# USDA_Project.net
KiCad netlist of a schematic drawn in EAGLE
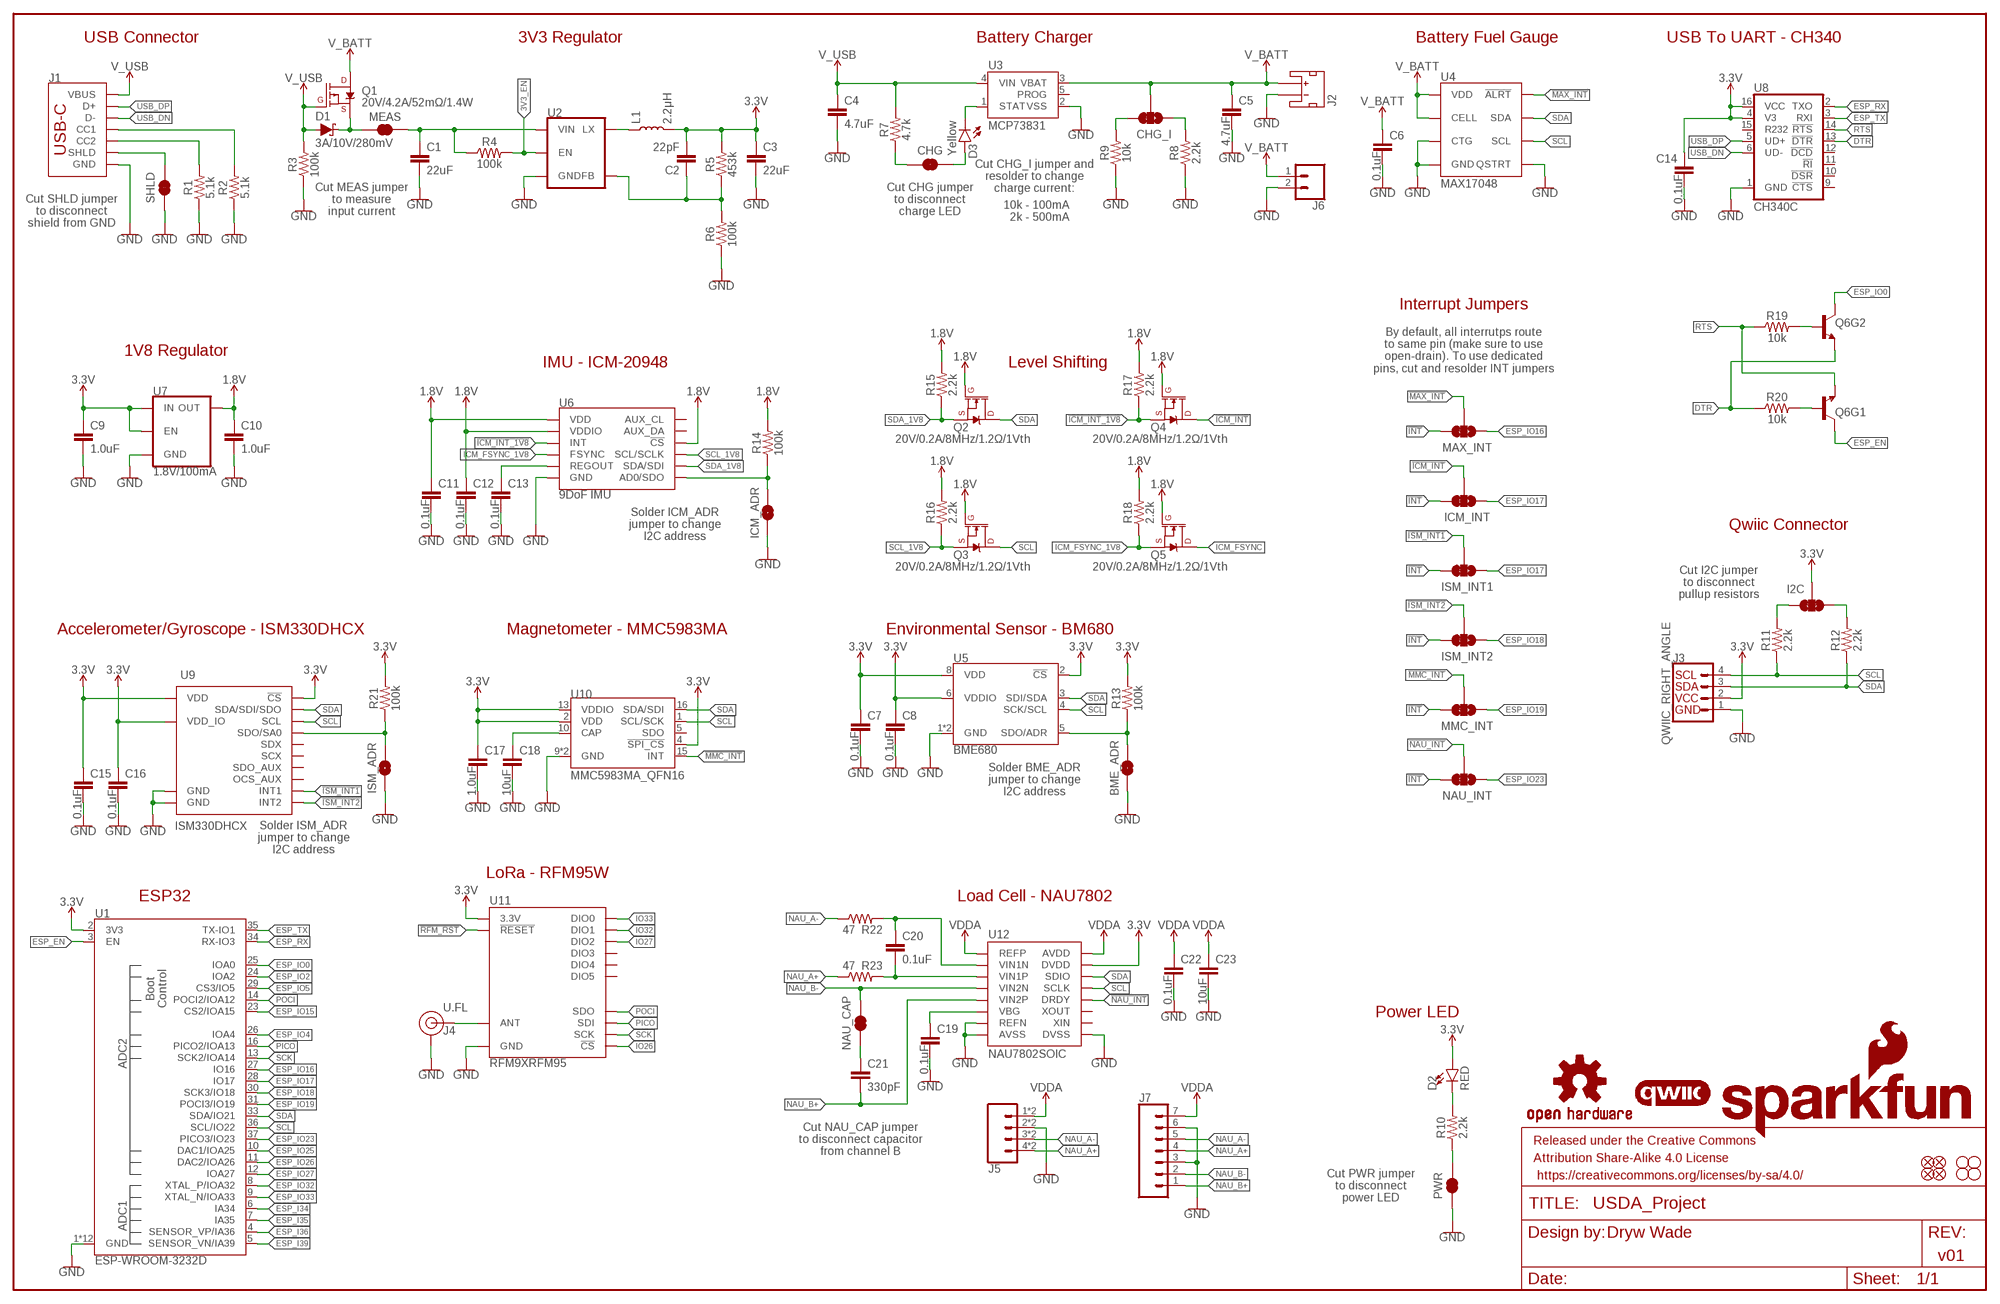
[diagram p0: schematic, sheet 1]

(export (version "E")
  (design (tool "Eeschema 10.0.6"))
  (components
    (comp (ref "BME_ADR")
      (value "JUMPER-SMT_2_NO_SILK")
      (footprint "eagle-import:SMT-JUMPER_2_NO_SILK")
      (libsource (lib "eagle-import") (part "JUMPER-SMT_2_NO_SILK"))
    )
    (comp (ref "C1")
      (value "22uF")
      (footprint "eagle-import:0805")
      (libsource (lib "eagle-import") (part "22UF-0805-16V-20%"))
    )
    (comp (ref "C2")
      (value "22pF")
      (footprint "eagle-import:0603")
      (libsource (lib "eagle-import") (part "22PF-0603-50V-5%"))
    )
    (comp (ref "C3")
      (value "22uF")
      (footprint "eagle-import:0805")
      (libsource (lib "eagle-import") (part "22UF-0805-16V-20%"))
    )
    (comp (ref "C4")
      (value "4.7uF")
      (footprint "eagle-import:0603")
      (libsource (lib "eagle-import") (part "4.7UF-0603-6.3V-(10%)"))
    )
    (comp (ref "C5")
      (value "4.7uF")
      (footprint "eagle-import:0603")
      (libsource (lib "eagle-import") (part "4.7UF-0603-6.3V-(10%)"))
    )
    (comp (ref "C6")
      (value "0.1uF")
      (footprint "eagle-import:0603")
      (libsource (lib "eagle-import") (part "0.1UF-0603-25V-(+80/-20%)"))
    )
    (comp (ref "C7")
      (value "0.1uF")
      (footprint "eagle-import:0603")
      (libsource (lib "eagle-import") (part "0.1UF-0603-25V-(+80/-20%)"))
    )
    (comp (ref "C8")
      (value "0.1uF")
      (footprint "eagle-import:0603")
      (libsource (lib "eagle-import") (part "0.1UF-0603-25V-(+80/-20%)"))
    )
    (comp (ref "C9")
      (value "1.0uF")
      (footprint "eagle-import:0603")
      (libsource (lib "eagle-import") (part "1.0UF-0603-16V-10%"))
    )
    (comp (ref "C10")
      (value "1.0uF")
      (footprint "eagle-import:0603")
      (libsource (lib "eagle-import") (part "1.0UF-0603-16V-10%"))
    )
    (comp (ref "C11")
      (value "0.1uF")
      (footprint "eagle-import:0603")
      (libsource (lib "eagle-import") (part "0.1UF-0603-25V-(+80/-20%)"))
    )
    (comp (ref "C12")
      (value "0.1uF")
      (footprint "eagle-import:0603")
      (libsource (lib "eagle-import") (part "0.1UF-0603-25V-(+80/-20%)"))
    )
    (comp (ref "C13")
      (value "0.1uF")
      (footprint "eagle-import:0603")
      (libsource (lib "eagle-import") (part "0.1UF-0603-25V-(+80/-20%)"))
    )
    (comp (ref "C14")
      (value "0.1uF")
      (footprint "eagle-import:0603")
      (libsource (lib "eagle-import") (part "0.1UF-0603-25V-(+80/-20%)"))
    )
    (comp (ref "C15")
      (value "0.1uF")
      (footprint "eagle-import:0603")
      (libsource (lib "eagle-import") (part "0.1UF-0603-25V-(+80/-20%)"))
    )
    (comp (ref "C16")
      (value "0.1uF")
      (footprint "eagle-import:0603")
      (libsource (lib "eagle-import") (part "0.1UF-0603-25V-(+80/-20%)"))
    )
    (comp (ref "C17")
      (value "1.0uF")
      (footprint "eagle-import:0603")
      (libsource (lib "eagle-import") (part "1.0UF-0603-16V-10%"))
    )
    (comp (ref "C18")
      (value "10uF")
      (footprint "eagle-import:0603")
      (libsource (lib "eagle-import") (part "10UF-0603-6.3V-20%"))
    )
    (comp (ref "C19")
      (value "0.1uF")
      (footprint "eagle-import:0603")
      (libsource (lib "eagle-import") (part "0.1UF-0603-25V-(+80/-20%)"))
    )
    (comp (ref "C20")
      (value "0.1uF")
      (footprint "eagle-import:0603")
      (libsource (lib "eagle-import") (part "0.1UF-0603-25V-(+80/-20%)"))
    )
    (comp (ref "C21")
      (value "330pF")
      (footprint "eagle-import:0603")
      (libsource (lib "eagle-import") (part "330PF-0603-50V-5%"))
    )
    (comp (ref "C22")
      (value "0.1uF")
      (footprint "eagle-import:0603")
      (libsource (lib "eagle-import") (part "0.1UF-0603-25V-(+80/-20%)"))
    )
    (comp (ref "C23")
      (value "10uF")
      (footprint "eagle-import:0603")
      (libsource (lib "eagle-import") (part "10UF-0603-6.3V-20%"))
    )
    (comp (ref "CHG")
      (value "JUMPER-SMT_2_NC_TRACE_SILK")
      (footprint "eagle-import:SMT-JUMPER_2_NC_TRACE_SILK")
      (libsource (lib "eagle-import") (part "JUMPER-SMT_2_NC_TRACE_SILK"))
    )
    (comp (ref "CHG_I")
      (value "JUMPER-SMT_3_1-NC_TRACE_SILK")
      (footprint "eagle-import:SMT-JUMPER_3_1-NC_TRACE_SILK")
      (libsource (lib "eagle-import") (part "JUMPER-SMT_3_1-NC_TRACE_SILK"))
    )
    (comp (ref "D1")
      (value "3A/10V/280mV")
      (footprint "eagle-import:SOD-323")
      (libsource (lib "eagle-import") (part "DIODE-SCHOTTKY-BAT60A"))
    )
    (comp (ref "D2")
      (value "RED")
      (footprint "eagle-import:LED-0603")
      (libsource (lib "eagle-import") (part "LED-RED0603"))
    )
    (comp (ref "D3")
      (value "Yellow")
      (footprint "eagle-import:LED-0603")
      (libsource (lib "eagle-import") (part "LED-YELLOW0603"))
    )
    (comp (ref "FD1")
      (value "FIDUCIAL1X2")
      (footprint "eagle-import:FIDUCIAL-1X2")
      (libsource (lib "eagle-import") (part "FIDUCIAL1X2"))
    )
    (comp (ref "FD2")
      (value "FIDUCIAL1X2")
      (footprint "eagle-import:FIDUCIAL-1X2")
      (libsource (lib "eagle-import") (part "FIDUCIAL1X2"))
    )
    (comp (ref "FD3")
      (value "FIDUCIAL1X2")
      (footprint "eagle-import:FIDUCIAL-1X2")
      (libsource (lib "eagle-import") (part "FIDUCIAL1X2"))
    )
    (comp (ref "FD4")
      (value "FIDUCIAL1X2")
      (footprint "eagle-import:FIDUCIAL-1X2")
      (libsource (lib "eagle-import") (part "FIDUCIAL1X2"))
    )
    (comp (ref "FRAME1")
      (value "FRAME-LEDGER")
      (footprint "eagle-import:CREATIVE_COMMONS")
      (libsource (lib "eagle-import") (part "FRAME-LEDGER"))
    )
    (comp (ref "H1")
      (value "STAND-OFF")
      (footprint "eagle-import:STAND-OFF")
      (libsource (lib "eagle-import") (part "STAND-OFF"))
    )
    (comp (ref "H2")
      (value "STAND-OFF")
      (footprint "eagle-import:STAND-OFF")
      (libsource (lib "eagle-import") (part "STAND-OFF"))
    )
    (comp (ref "H3")
      (value "STAND-OFF")
      (footprint "eagle-import:STAND-OFF")
      (libsource (lib "eagle-import") (part "STAND-OFF"))
    )
    (comp (ref "H4")
      (value "STAND-OFF")
      (footprint "eagle-import:STAND-OFF")
      (libsource (lib "eagle-import") (part "STAND-OFF"))
    )
    (comp (ref "I2C")
      (value "JUMPER-SMT_3_2-NC_TRACE_SILK")
      (footprint "eagle-import:SMT-JUMPER_3_2-NC_TRACE_SILK")
      (libsource (lib "eagle-import") (part "JUMPER-SMT_3_2-NC_TRACE_SILK"))
    )
    (comp (ref "ICM_ADR")
      (value "JUMPER-SMT_2_NO_SILK")
      (footprint "eagle-import:SMT-JUMPER_2_NO_SILK")
      (libsource (lib "eagle-import") (part "JUMPER-SMT_2_NO_SILK"))
    )
    (comp (ref "ICM_INT")
      (value "JUMPER-SMT_3_1-NC_TRACE_SILK")
      (footprint "eagle-import:SMT-JUMPER_3_1-NC_TRACE_SILK")
      (libsource (lib "eagle-import") (part "JUMPER-SMT_3_1-NC_TRACE_SILK"))
    )
    (comp (ref "ISM_ADR")
      (value "JUMPER-SMT_2_NO_SILK")
      (footprint "eagle-import:SMT-JUMPER_2_NO_SILK")
      (libsource (lib "eagle-import") (part "JUMPER-SMT_2_NO_SILK"))
    )
    (comp (ref "ISM_INT1")
      (value "JUMPER-SMT_3_1-NC_TRACE_SILK")
      (footprint "eagle-import:SMT-JUMPER_3_1-NC_TRACE_SILK")
      (libsource (lib "eagle-import") (part "JUMPER-SMT_3_1-NC_TRACE_SILK"))
    )
    (comp (ref "ISM_INT2")
      (value "JUMPER-SMT_3_1-NC_TRACE_SILK")
      (footprint "eagle-import:SMT-JUMPER_3_1-NC_TRACE_SILK")
      (libsource (lib "eagle-import") (part "JUMPER-SMT_3_1-NC_TRACE_SILK"))
    )
    (comp (ref "J1")
      (value "USB_C_2-LAYER_PADS")
      (footprint "eagle-import:USB-C-16P-2LAYER-PADS")
      (libsource (lib "eagle-import") (part "USB_C_2-LAYER_PADS"))
    )
    (comp (ref "J2")
      (value "JST_2MM_MALE")
      (footprint "eagle-import:JST-2-SMD")
      (libsource (lib "eagle-import") (part "JST_2MM_MALE"))
    )
    (comp (ref "J3")
      (value "QWIIC_RIGHT_ANGLE")
      (footprint "eagle-import:JST04_1MM_RA")
      (libsource (lib "eagle-import") (part "QWIIC_CONNECTORJS-1MM"))
    )
    (comp (ref "J4")
      (value "U.FL")
      (footprint "eagle-import:U.FL")
      (libsource (lib "eagle-import") (part "U.FL2PIN"))
    )
    (comp (ref "J5")
      (value "CONN_04SPRING")
      (footprint "eagle-import:1X04_SPRING_TERMINAL")
      (libsource (lib "eagle-import") (part "CONN_04SPRING"))
    )
    (comp (ref "J6")
      (value "CONN_021X02_NO_SILK")
      (footprint "eagle-import:1X02_NO_SILK")
      (libsource (lib "eagle-import") (part "CONN_021X02_NO_SILK"))
    )
    (comp (ref "J7")
      (value "CONN_07NO_SILK")
      (footprint "eagle-import:1X07_NO_SILK")
      (libsource (lib "eagle-import") (part "CONN_07NO_SILK"))
    )
    (comp (ref "L1")
      (value "2.2μH")
      (footprint "eagle-import:INDUCTOR_4X4MM")
      (libsource (lib "eagle-import") (part "2.2μH-4X4-2.2μH-3A-45MOHM"))
    )
    (comp (ref "LOGO1")
      (value "SFE_LOGO_NAME_FLAME.1_INCH")
      (footprint "eagle-import:SFE_LOGO_NAME_FLAME_.1")
      (libsource (lib "eagle-import") (part "SFE_LOGO_NAME_FLAME.1_INCH"))
    )
    (comp (ref "LOGO2")
      (value "OSHW-LOGOS")
      (footprint "eagle-import:OSHW-LOGO-S")
      (libsource (lib "eagle-import") (part "OSHW-LOGOS"))
    )
    (comp (ref "LOGO3")
      (value "QWIIC_LOGO_5MM")
      (footprint "eagle-import:QWIIC_5MM")
      (libsource (lib "eagle-import") (part "QWIIC_LOGO_5MM"))
    )
    (comp (ref "MAX_INT")
      (value "JUMPER-SMT_3_1-NC_TRACE_SILK")
      (footprint "eagle-import:SMT-JUMPER_3_1-NC_TRACE_SILK")
      (libsource (lib "eagle-import") (part "JUMPER-SMT_3_1-NC_TRACE_SILK"))
    )
    (comp (ref "MEAS")
      (value "JUMPER-COMBO_2_NC_TRACE")
      (footprint "eagle-import:COMBO-JUMPER_2_NC_TRACE")
      (libsource (lib "eagle-import") (part "JUMPER-COMBO_2_NC_TRACE"))
    )
    (comp (ref "MMC_INT")
      (value "JUMPER-SMT_3_1-NC_TRACE_SILK")
      (footprint "eagle-import:SMT-JUMPER_3_1-NC_TRACE_SILK")
      (libsource (lib "eagle-import") (part "JUMPER-SMT_3_1-NC_TRACE_SILK"))
    )
    (comp (ref "NAU_CAP")
      (value "JUMPER-SMT_2_NC_TRACE_SILK")
      (footprint "eagle-import:SMT-JUMPER_2_NC_TRACE_SILK")
      (libsource (lib "eagle-import") (part "JUMPER-SMT_2_NC_TRACE_SILK"))
    )
    (comp (ref "NAU_INT")
      (value "JUMPER-SMT_3_1-NC_TRACE_SILK")
      (footprint "eagle-import:SMT-JUMPER_3_1-NC_TRACE_SILK")
      (libsource (lib "eagle-import") (part "JUMPER-SMT_3_1-NC_TRACE_SILK"))
    )
    (comp (ref "PWR")
      (value "JUMPER-SMT_2_NC_TRACE_SILK")
      (footprint "eagle-import:SMT-JUMPER_2_NC_TRACE_SILK")
      (libsource (lib "eagle-import") (part "JUMPER-SMT_2_NC_TRACE_SILK"))
    )
    (comp (ref "Q1")
      (value "20V/4.2A/52mΩ/1.4W")
      (footprint "eagle-import:SOT23-3")
      (libsource (lib "eagle-import") (part "MOSFET_PCH-DMG2305UX-7"))
    )
    (comp (ref "Q2")
      (value "20V/0.2A/8MHz/1.2Ω/1Vth")
      (footprint "eagle-import:SOT-416FL")
      (libsource (lib "eagle-import") (part "MOSFET-NCH-RE1C002UNTCL"))
    )
    (comp (ref "Q3")
      (value "20V/0.2A/8MHz/1.2Ω/1Vth")
      (footprint "eagle-import:SOT-416FL")
      (libsource (lib "eagle-import") (part "MOSFET-NCH-RE1C002UNTCL"))
    )
    (comp (ref "Q4")
      (value "20V/0.2A/8MHz/1.2Ω/1Vth")
      (footprint "eagle-import:SOT-416FL")
      (libsource (lib "eagle-import") (part "MOSFET-NCH-RE1C002UNTCL"))
    )
    (comp (ref "Q5")
      (value "20V/0.2A/8MHz/1.2Ω/1Vth")
      (footprint "eagle-import:SOT-416FL")
      (libsource (lib "eagle-import") (part "MOSFET-NCH-RE1C002UNTCL"))
    )
    (comp (ref "Q6")
      (value "TRANS_NPN_DUAL-MBT3904DW1T1")
      (footprint "eagle-import:SC70-6")
      (libsource (lib "eagle-import") (part "TRANS_NPN_DUAL-MBT3904DW1T1"))
    )
    (comp (ref "R1")
      (value "5.1k")
      (footprint "eagle-import:0603")
      (libsource (lib "eagle-import") (part "5.1KOHM5.1KOHM-0603-1/10W-1%"))
    )
    (comp (ref "R2")
      (value "5.1k")
      (footprint "eagle-import:0603")
      (libsource (lib "eagle-import") (part "5.1KOHM5.1KOHM-0603-1/10W-1%"))
    )
    (comp (ref "R3")
      (value "100k")
      (footprint "eagle-import:0603")
      (libsource (lib "eagle-import") (part "100KOHM-0603-1/10W-1%"))
    )
    (comp (ref "R4")
      (value "100k")
      (footprint "eagle-import:0603")
      (libsource (lib "eagle-import") (part "100KOHM-0603-1/10W-1%"))
    )
    (comp (ref "R5")
      (value "453k")
      (footprint "eagle-import:0603")
      (libsource (lib "eagle-import") (part "453KOHM-0603-1/10W-1%"))
    )
    (comp (ref "R6")
      (value "100k")
      (footprint "eagle-import:0603")
      (libsource (lib "eagle-import") (part "100KOHM-0603-1/10W-1%"))
    )
    (comp (ref "R7")
      (value "4.7k")
      (footprint "eagle-import:0603")
      (libsource (lib "eagle-import") (part "4.7KOHM-0603-1/10W-1%"))
    )
    (comp (ref "R8")
      (value "2.2k")
      (footprint "eagle-import:0603")
      (libsource (lib "eagle-import") (part "2.2KOHM-0603-1/10W-1%"))
    )
    (comp (ref "R9")
      (value "10k")
      (footprint "eagle-import:0603")
      (libsource (lib "eagle-import") (part "10KOHM-0603-1/10W-1%"))
    )
    (comp (ref "R10")
      (value "2.2k")
      (footprint "eagle-import:0603")
      (libsource (lib "eagle-import") (part "2.2KOHM-0603-1/10W-1%"))
    )
    (comp (ref "R11")
      (value "2.2k")
      (footprint "eagle-import:0603")
      (libsource (lib "eagle-import") (part "2.2KOHM-0603-1/10W-1%"))
    )
    (comp (ref "R12")
      (value "2.2k")
      (footprint "eagle-import:0603")
      (libsource (lib "eagle-import") (part "2.2KOHM-0603-1/10W-1%"))
    )
    (comp (ref "R13")
      (value "100k")
      (footprint "eagle-import:0603")
      (libsource (lib "eagle-import") (part "100KOHM-0603-1/10W-1%"))
    )
    (comp (ref "R14")
      (value "100k")
      (footprint "eagle-import:0603")
      (libsource (lib "eagle-import") (part "100KOHM-0603-1/10W-1%"))
    )
    (comp (ref "R15")
      (value "2.2k")
      (footprint "eagle-import:0603")
      (libsource (lib "eagle-import") (part "2.2KOHM-0603-1/10W-1%"))
    )
    (comp (ref "R16")
      (value "2.2k")
      (footprint "eagle-import:0603")
      (libsource (lib "eagle-import") (part "2.2KOHM-0603-1/10W-1%"))
    )
    (comp (ref "R17")
      (value "2.2k")
      (footprint "eagle-import:0603")
      (libsource (lib "eagle-import") (part "2.2KOHM-0603-1/10W-1%"))
    )
    (comp (ref "R18")
      (value "2.2k")
      (footprint "eagle-import:0603")
      (libsource (lib "eagle-import") (part "2.2KOHM-0603-1/10W-1%"))
    )
    (comp (ref "R19")
      (value "10k")
      (footprint "eagle-import:0603")
      (libsource (lib "eagle-import") (part "10KOHM-0603-1/10W-1%"))
    )
    (comp (ref "R20")
      (value "10k")
      (footprint "eagle-import:0603")
      (libsource (lib "eagle-import") (part "10KOHM-0603-1/10W-1%"))
    )
    (comp (ref "R21")
      (value "100k")
      (footprint "eagle-import:0603")
      (libsource (lib "eagle-import") (part "100KOHM-0603-1/10W-1%"))
    )
    (comp (ref "R22")
      (value "47")
      (footprint "eagle-import:0603")
      (libsource (lib "eagle-import") (part "47OHM-0603-1/10W-1%"))
    )
    (comp (ref "R23")
      (value "47")
      (footprint "eagle-import:0603")
      (libsource (lib "eagle-import") (part "47OHM-0603-1/10W-1%"))
    )
    (comp (ref "SHLD")
      (value "JUMPER-SMT_2_NC_TRACE_SILK")
      (footprint "eagle-import:SMT-JUMPER_2_NC_TRACE_SILK")
      (libsource (lib "eagle-import") (part "JUMPER-SMT_2_NC_TRACE_SILK"))
    )
    (comp (ref "U1")
      (value "ESP-WROOM-3232D")
      (footprint "eagle-import:ESP-WROOM-32D")
      (libsource (lib "eagle-import") (part "ESP-WROOM-3232D"))
    )
    (comp (ref "U2")
      (value "AP3429/A")
      (footprint "eagle-import:SOT23-5")
      (libsource (lib "eagle-import") (part "AP3429/A"))
    )
    (comp (ref "U3")
      (value "MCP73831")
      (footprint "eagle-import:SOT23-5")
      (libsource (lib "eagle-import") (part "MCP73831"))
    )
    (comp (ref "U4")
      (value "MAX17048")
      (footprint "eagle-import:DFN-8")
      (libsource (lib "eagle-import") (part "MAX17048DFN8"))
    )
    (comp (ref "U5")
      (value "BME680")
      (footprint "eagle-import:LGA3.0X3.0")
      (libsource (lib "eagle-import") (part "BME680-LGA"))
    )
    (comp (ref "U6")
      (value "9DoF IMU")
      (footprint "eagle-import:QFN24-3X3-ICM-20948")
      (libsource (lib "eagle-import") (part "ICM-20948"))
    )
    (comp (ref "U7")
      (value "1.8V/100mA")
      (footprint "eagle-import:SC70")
      (libsource (lib "eagle-import") (part "V_REG_SP6214-1.8V"))
    )
    (comp (ref "U8")
      (value "CH340C")
      (footprint "eagle-import:SO016")
      (libsource (lib "eagle-import") (part "CH340C"))
    )
    (comp (ref "U9")
      (value "ISM330DHCX")
      (footprint "eagle-import:LGA-14L")
      (libsource (lib "eagle-import") (part "ISM330DHCX"))
    )
    (comp (ref "U10")
      (value "MMC5983MA_QFN16")
      (footprint "eagle-import:LGA-16-3X3MM-4X4PINS")
      (libsource (lib "eagle-import") (part "MMC5983MA_QFN16"))
    )
    (comp (ref "U11")
      (value "RFM9XRFM95")
      (footprint "eagle-import:RFM95")
      (libsource (lib "eagle-import") (part "RFM9XRFM95"))
    )
    (comp (ref "U12")
      (value "NAU7802SOIC")
      (footprint "eagle-import:SO16")
      (libsource (lib "eagle-import") (part "NAU7802SOIC"))
    )
  )
  (nets
    (net (code "1") (name "/~{ICM_INT_1V8}") (class "Default")
      (node (ref "Q4") (pin "2") (pinfunction "S_2") (pintype "bidirectional"))
      (node (ref "R17") (pin "1") (pinfunction "1_1") (pintype "passive"))
      (node (ref "U6") (pin "12") (pinfunction "INT_12") (pintype "bidirectional"))
    )
    (net (code "2") (name "/~{ICM_INT}") (class "Default")
      (node (ref "ICM_INT") (pin "2") (pinfunction "2_2") (pintype "passive"))
      (node (ref "Q4") (pin "3") (pinfunction "D_3") (pintype "bidirectional"))
    )
    (net (code "3") (name "/~{INT}") (class "Default")
      (node (ref "ICM_INT") (pin "3") (pinfunction "3_3") (pintype "passive"))
      (node (ref "ISM_INT1") (pin "3") (pinfunction "3_3") (pintype "passive"))
      (node (ref "ISM_INT2") (pin "3") (pinfunction "3_3") (pintype "passive"))
      (node (ref "MAX_INT") (pin "3") (pinfunction "3_3") (pintype "passive"))
      (node (ref "MMC_INT") (pin "3") (pinfunction "3_3") (pintype "passive"))
      (node (ref "NAU_INT") (pin "3") (pinfunction "3_3") (pintype "passive"))
    )
    (net (code "4") (name "/~{ISM_INT1}") (class "Default")
      (node (ref "ISM_INT1") (pin "2") (pinfunction "2_2") (pintype "passive"))
      (node (ref "U9") (pin "P4") (pinfunction "INT1_P4") (pintype "bidirectional"))
    )
    (net (code "5") (name "/~{ISM_INT2}") (class "Default")
      (node (ref "ISM_INT2") (pin "2") (pinfunction "2_2") (pintype "passive"))
      (node (ref "U9") (pin "P9") (pinfunction "INT2_P9") (pintype "bidirectional"))
    )
    (net (code "6") (name "/~{MAX_INT}") (class "Default")
      (node (ref "MAX_INT") (pin "2") (pinfunction "2_2") (pintype "passive"))
      (node (ref "U4") (pin "5") (pinfunction "~{ALRT}_5") (pintype "bidirectional"))
    )
    (net (code "7") (name "/~{MMC_INT}") (class "Default")
      (node (ref "MMC_INT") (pin "2") (pinfunction "2_2") (pintype "passive"))
      (node (ref "U10") (pin "15") (pinfunction "INT_15") (pintype "output"))
    )
    (net (code "8") (name "/~{NAU_INT}") (class "Default")
      (node (ref "NAU_INT") (pin "2") (pinfunction "2_2") (pintype "passive"))
      (node (ref "U12") (pin "12") (pinfunction "DRDY_12") (pintype "bidirectional"))
    )
    (net (code "9") (name "/~{RFM_RST}") (class "Default")
      (node (ref "U11") (pin "!RESET") (pinfunction "~{RESET}_!RESET") (pintype "bidirectional"))
    )
    (net (code "10") (name "1.8V") (class "Default")
      (node (ref "C10") (pin "1") (pinfunction "1_1") (pintype "passive"))
      (node (ref "C11") (pin "1") (pinfunction "1_1") (pintype "passive"))
      (node (ref "C12") (pin "1") (pinfunction "1_1") (pintype "passive"))
      (node (ref "Q2") (pin "1") (pinfunction "G_1") (pintype "bidirectional"))
      (node (ref "Q3") (pin "1") (pinfunction "G_1") (pintype "bidirectional"))
      (node (ref "Q4") (pin "1") (pinfunction "G_1") (pintype "bidirectional"))
      (node (ref "Q5") (pin "1") (pinfunction "G_1") (pintype "bidirectional"))
      (node (ref "R14") (pin "2") (pinfunction "2_2") (pintype "passive"))
      (node (ref "R15") (pin "2") (pinfunction "2_2") (pintype "passive"))
      (node (ref "R16") (pin "2") (pinfunction "2_2") (pintype "passive"))
      (node (ref "R17") (pin "2") (pinfunction "2_2") (pintype "passive"))
      (node (ref "R18") (pin "2") (pinfunction "2_2") (pintype "passive"))
      (node (ref "U6") (pin "13") (pinfunction "VDD_13") (pintype "bidirectional"))
      (node (ref "U6") (pin "22") (pinfunction "~{CS}_22") (pintype "bidirectional"))
      (node (ref "U6") (pin "8") (pinfunction "VDDIO_8") (pintype "bidirectional"))
      (node (ref "U7") (pin "5") (pinfunction "OUT_5") (pintype "passive"))
    )
    (net (code "11") (name "3.3V") (class "Default")
      (node (ref "C14") (pin "1") (pinfunction "1_1") (pintype "passive"))
      (node (ref "C15") (pin "1") (pinfunction "1_1") (pintype "passive"))
      (node (ref "C16") (pin "1") (pinfunction "1_1") (pintype "passive"))
      (node (ref "C17") (pin "1") (pinfunction "1_1") (pintype "passive"))
      (node (ref "C2") (pin "2") (pinfunction "2_2") (pintype "passive"))
      (node (ref "C3") (pin "1") (pinfunction "1_1") (pintype "passive"))
      (node (ref "C7") (pin "1") (pinfunction "1_1") (pintype "passive"))
      (node (ref "C8") (pin "1") (pinfunction "1_1") (pintype "passive"))
      (node (ref "C9") (pin "1") (pinfunction "1_1") (pintype "passive"))
      (node (ref "D2") (pin "A") (pinfunction "A_A") (pintype "passive"))
      (node (ref "I2C") (pin "2") (pinfunction "2_2") (pintype "passive"))
      (node (ref "J3") (pin "2") (pinfunction "2_2") (pintype "power_in"))
      (node (ref "L1") (pin "P$2") (pinfunction "2_P$2") (pintype "passive"))
      (node (ref "R13") (pin "2") (pinfunction "2_2") (pintype "passive"))
      (node (ref "R21") (pin "2") (pinfunction "2_2") (pintype "passive"))
      (node (ref "R5") (pin "2") (pinfunction "2_2") (pintype "passive"))
      (node (ref "U1") (pin "2") (pinfunction "3V3_2") (pintype "bidirectional"))
      (node (ref "U10") (pin "13") (pinfunction "VDDIO_13") (pintype "power_in"))
      (node (ref "U10") (pin "2") (pinfunction "VDD_2") (pintype "power_in"))
      (node (ref "U10") (pin "4") (pinfunction "~{SPI_CS}_4") (pintype "input"))
      (node (ref "U11") (pin "3.3V") (pinfunction "3.3V_3.3V") (pintype "bidirectional"))
      (node (ref "U12") (pin "15") (pinfunction "DVDD_15") (pintype "bidirectional"))
      (node (ref "U5") (pin "2") (pinfunction "~{CS}_2") (pintype "bidirectional"))
      (node (ref "U5") (pin "6") (pinfunction "VDDIO_6") (pintype "bidirectional"))
      (node (ref "U5") (pin "8") (pinfunction "VDD_8") (pintype "bidirectional"))
      (node (ref "U7") (pin "1") (pinfunction "IN_1") (pintype "input"))
      (node (ref "U7") (pin "3") (pinfunction "EN_3") (pintype "input"))
      (node (ref "U8") (pin "16") (pinfunction "VCC_16") (pintype "bidirectional"))
      (node (ref "U8") (pin "4") (pinfunction "V3_4") (pintype "bidirectional"))
      (node (ref "U9") (pin "P12") (pinfunction "~{CS}_P12") (pintype "bidirectional"))
      (node (ref "U9") (pin "P5") (pinfunction "VDD_IO_P5") (pintype "power_in"))
      (node (ref "U9") (pin "P8") (pinfunction "VDD_P8") (pintype "power_in"))
    )
    (net (code "12") (name "3V3_EN") (class "Default")
      (node (ref "R4") (pin "2") (pinfunction "2_2") (pintype "passive"))
      (node (ref "U2") (pin "1") (pinfunction "EN_1") (pintype "input"))
    )
    (net (code "13") (name "DTR") (class "Default")
      (node (ref "Q6") (pin "1") (pinfunction "E_1") (pintype "passive"))
      (node (ref "R20") (pin "1") (pinfunction "1_1") (pintype "passive"))
      (node (ref "U8") (pin "13") (pinfunction "~{DTR}_13") (pintype "bidirectional"))
    )
    (net (code "14") (name "ESP_EN") (class "Default")
      (node (ref "Q6") (pin "3") (pinfunction "C_3") (pintype "passive"))
      (node (ref "U1") (pin "3") (pinfunction "EN_3") (pintype "bidirectional"))
    )
    (net (code "15") (name "ESP_I34") (class "Default")
      (node (ref "U1") (pin "6") (pinfunction "IA34_6") (pintype "bidirectional"))
    )
    (net (code "16") (name "ESP_I35") (class "Default")
      (node (ref "U1") (pin "7") (pinfunction "IA35_7") (pintype "bidirectional"))
    )
    (net (code "17") (name "ESP_I36") (class "Default")
      (node (ref "U1") (pin "4") (pinfunction "SENSOR_VP/IA36_4") (pintype "bidirectional"))
    )
    (net (code "18") (name "ESP_I39") (class "Default")
      (node (ref "U1") (pin "5") (pinfunction "SENSOR_VN/IA39_5") (pintype "bidirectional"))
    )
    (net (code "19") (name "ESP_IO0") (class "Default")
      (node (ref "Q6") (pin "6") (pinfunction "C_6") (pintype "passive"))
      (node (ref "U1") (pin "25") (pinfunction "IOA0_25") (pintype "bidirectional"))
    )
    (net (code "20") (name "ESP_IO2") (class "Default")
      (node (ref "U1") (pin "24") (pinfunction "IOA2_24") (pintype "bidirectional"))
    )
    (net (code "21") (name "ESP_IO4") (class "Default")
      (node (ref "U1") (pin "26") (pinfunction "IOA4_26") (pintype "bidirectional"))
    )
    (net (code "22") (name "ESP_IO5") (class "Default")
      (node (ref "U1") (pin "29") (pinfunction "CS3/IO5_29") (pintype "bidirectional"))
    )
    (net (code "23") (name "ESP_IO15") (class "Default")
      (node (ref "U1") (pin "23") (pinfunction "CS2/IOA15_23") (pintype "bidirectional"))
    )
    (net (code "24") (name "ESP_IO16") (class "Default")
      (node (ref "MAX_INT") (pin "1") (pinfunction "1_1") (pintype "passive"))
      (node (ref "U1") (pin "27") (pinfunction "IO16_27") (pintype "bidirectional"))
    )
    (net (code "25") (name "ESP_IO17") (class "Default")
      (node (ref "ICM_INT") (pin "1") (pinfunction "1_1") (pintype "passive"))
      (node (ref "ISM_INT1") (pin "1") (pinfunction "1_1") (pintype "passive"))
      (node (ref "U1") (pin "28") (pinfunction "IO17_28") (pintype "bidirectional"))
    )
    (net (code "26") (name "ESP_IO18") (class "Default")
      (node (ref "ISM_INT2") (pin "1") (pinfunction "1_1") (pintype "passive"))
      (node (ref "U1") (pin "30") (pinfunction "SCK3/IO18_30") (pintype "bidirectional"))
    )
    (net (code "27") (name "ESP_IO19") (class "Default")
      (node (ref "MMC_INT") (pin "1") (pinfunction "1_1") (pintype "passive"))
      (node (ref "U1") (pin "31") (pinfunction "POCI3/IO19_31") (pintype "bidirectional"))
    )
    (net (code "28") (name "ESP_IO23") (class "Default")
      (node (ref "NAU_INT") (pin "1") (pinfunction "1_1") (pintype "passive"))
      (node (ref "U1") (pin "37") (pinfunction "PICO3/IO23_37") (pintype "bidirectional"))
    )
    (net (code "29") (name "ESP_IO25") (class "Default")
      (node (ref "U1") (pin "10") (pinfunction "DAC1/IOA25_10") (pintype "bidirectional"))
    )
    (net (code "30") (name "ESP_IO26") (class "Default")
      (node (ref "U1") (pin "11") (pinfunction "DAC2/IOA26_11") (pintype "bidirectional"))
    )
    (net (code "31") (name "ESP_IO27") (class "Default")
      (node (ref "U1") (pin "12") (pinfunction "IOA27_12") (pintype "bidirectional"))
    )
    (net (code "32") (name "ESP_IO32") (class "Default")
      (node (ref "U1") (pin "8") (pinfunction "XTAL_P/IOA32_8") (pintype "bidirectional"))
    )
    (net (code "33") (name "ESP_IO33") (class "Default")
      (node (ref "U1") (pin "9") (pinfunction "XTAL_N/IOA33_9") (pintype "bidirectional"))
    )
    (net (code "34") (name "ESP_RX") (class "Default")
      (node (ref "U1") (pin "34") (pinfunction "RX-IO3_34") (pintype "bidirectional"))
      (node (ref "U8") (pin "2") (pinfunction "TXO_2") (pintype "bidirectional"))
    )
    (net (code "35") (name "ESP_TX") (class "Default")
      (node (ref "U1") (pin "35") (pinfunction "TX-IO1_35") (pintype "bidirectional"))
      (node (ref "U8") (pin "3") (pinfunction "RXI_3") (pintype "bidirectional"))
    )
    (net (code "36") (name "GND") (class "Default")
      (node (ref "BME_ADR") (pin "1") (pinfunction "1_1") (pintype "passive"))
      (node (ref "C1") (pin "2") (pinfunction "2_2") (pintype "passive"))
      (node (ref "C10") (pin "2") (pinfunction "2_2") (pintype "passive"))
      (node (ref "C11") (pin "2") (pinfunction "2_2") (pintype "passive"))
      (node (ref "C12") (pin "2") (pinfunction "2_2") (pintype "passive"))
      (node (ref "C13") (pin "2") (pinfunction "2_2") (pintype "passive"))
      (node (ref "C14") (pin "2") (pinfunction "2_2") (pintype "passive"))
      (node (ref "C15") (pin "2") (pinfunction "2_2") (pintype "passive"))
      (node (ref "C16") (pin "2") (pinfunction "2_2") (pintype "passive"))
      (node (ref "C17") (pin "2") (pinfunction "2_2") (pintype "passive"))
      (node (ref "C18") (pin "2") (pinfunction "2_2") (pintype "passive"))
      (node (ref "C19") (pin "2") (pinfunction "2_2") (pintype "passive"))
      (node (ref "C22") (pin "2") (pinfunction "2_2") (pintype "passive"))
      (node (ref "C23") (pin "2") (pinfunction "2_2") (pintype "passive"))
      (node (ref "C3") (pin "2") (pinfunction "2_2") (pintype "passive"))
      (node (ref "C4") (pin "2") (pinfunction "2_2") (pintype "passive"))
      (node (ref "C5") (pin "2") (pinfunction "2_2") (pintype "passive"))
      (node (ref "C6") (pin "2") (pinfunction "2_2") (pintype "passive"))
      (node (ref "C7") (pin "2") (pinfunction "2_2") (pintype "passive"))
      (node (ref "C8") (pin "2") (pinfunction "2_2") (pintype "passive"))
      (node (ref "C9") (pin "2") (pinfunction "2_2") (pintype "passive"))
      (node (ref "ICM_ADR") (pin "1") (pinfunction "1_1") (pintype "passive"))
      (node (ref "ISM_ADR") (pin "1") (pinfunction "1_1") (pintype "passive"))
      (node (ref "J1") (pin "GND") (pinfunction "GND_GND") (pintype "bidirectional"))
      (node (ref "J1") (pin "GND2") (pinfunction "GND_GND2") (pintype "bidirectional"))
      (node (ref "J2") (pin "1") (pinfunction "-_1") (pintype "bidirectional"))
      (node (ref "J3") (pin "1") (pinfunction "1_1") (pintype "power_in"))
      (node (ref "J4") (pin "1") (pinfunction "GND_1") (pintype "bidirectional"))
      (node (ref "J4") (pin "2") (pinfunction "GND_2") (pintype "bidirectional"))
      (node (ref "J5") (pin "2") (pinfunction "2_2") (pintype "passive"))
      (node (ref "J5") (pin "6") (pinfunction "2_6") (pintype "passive"))
      (node (ref "J6") (pin "2") (pinfunction "2_2") (pintype "passive"))
      (node (ref "J7") (pin "3") (pinfunction "3_3") (pintype "passive"))
      (node (ref "J7") (pin "6") (pinfunction "6_6") (pintype "passive"))
      (node (ref "PWR") (pin "1") (pinfunction "1_1") (pintype "passive"))
      (node (ref "R1") (pin "1") (pinfunction "1_1") (pintype "passive"))
      (node (ref "R2") (pin "1") (pinfunction "1_1") (pintype "passive"))
      (node (ref "R3") (pin "1") (pinfunction "1_1") (pintype "passive"))
      (node (ref "R6") (pin "1") (pinfunction "1_1") (pintype "passive"))
      (node (ref "R8") (pin "1") (pinfunction "1_1") (pintype "passive"))
      (node (ref "R9") (pin "1") (pinfunction "1_1") (pintype "passive"))
      (node (ref "SHLD") (pin "1") (pinfunction "1_1") (pintype "passive"))
      (node (ref "U1") (pin "1") (pinfunction "GND_1") (pintype "bidirectional"))
      (node (ref "U1") (pin "15") (pinfunction "GND_15") (pintype "bidirectional"))
      (node (ref "U1") (pin "38") (pinfunction "GND_38") (pintype "bidirectional"))
      (node (ref "U1") (pin "GND") (pinfunction "GND_GND") (pintype "bidirectional"))
      (node (ref "U1") (pin "GNDT1") (pinfunction "GND_GNDT1") (pintype "bidirectional"))
      (node (ref "U1") (pin "GNDT2") (pinfunction "GND_GNDT2") (pintype "bidirectional"))
      (node (ref "U1") (pin "GNDT3") (pinfunction "GND_GNDT3") (pintype "bidirectional"))
      (node (ref "U1") (pin "GNDT4") (pinfunction "GND_GNDT4") (pintype "bidirectional"))
      (node (ref "U1") (pin "GNDT5") (pinfunction "GND_GNDT5") (pintype "bidirectional"))
      (node (ref "U1") (pin "GNDT6") (pinfunction "GND_GNDT6") (pintype "bidirectional"))
      (node (ref "U1") (pin "GNDT7") (pinfunction "GND_GNDT7") (pintype "bidirectional"))
      (node (ref "U1") (pin "GNDT8") (pinfunction "GND_GNDT8") (pintype "bidirectional"))
      (node (ref "U10") (pin "11") (pinfunction "GND_11") (pintype "power_in"))
      (node (ref "U10") (pin "9") (pinfunction "GND_9") (pintype "power_in"))
      (node (ref "U11") (pin "GND@1") (pinfunction "GND_GND@1") (pintype "bidirectional"))
      (node (ref "U11") (pin "GND@2") (pinfunction "GND_GND@2") (pintype "bidirectional"))
      (node (ref "U11") (pin "GND@3") (pinfunction "GND_GND@3") (pintype "bidirectional"))
      (node (ref "U12") (pin "7") (pinfunction "REFN_7") (pintype "bidirectional"))
      (node (ref "U12") (pin "8") (pinfunction "AVSS_8") (pintype "bidirectional"))
      (node (ref "U12") (pin "9") (pinfunction "DVSS_9") (pintype "bidirectional"))
      (node (ref "U2") (pin "2") (pinfunction "GND_2") (pintype "input"))
      (node (ref "U3") (pin "2") (pinfunction "VSS_2") (pintype "power_in"))
      (node (ref "U4") (pin "1") (pinfunction "CTG_1") (pintype "input"))
      (node (ref "U4") (pin "4") (pinfunction "GND_4") (pintype "bidirectional"))
      (node (ref "U4") (pin "6") (pinfunction "QSTRT_6") (pintype "bidirectional"))
      (node (ref "U4") (pin "9") (pinfunction "GND_9") (pintype "bidirectional"))
      (node (ref "U5") (pin "1") (pinfunction "GND_1") (pintype "bidirectional"))
      (node (ref "U5") (pin "7") (pinfunction "GND_7") (pintype "bidirectional"))
      (node (ref "U6") (pin "18") (pinfunction "GND_18") (pintype "bidirectional"))
      (node (ref "U6") (pin "20") (pinfunction "GND_20") (pintype "bidirectional"))
      (node (ref "U7") (pin "2") (pinfunction "GND_2") (pintype "input"))
      (node (ref "U8") (pin "1") (pinfunction "GND_1") (pintype "bidirectional"))
      (node (ref "U9") (pin "P6") (pinfunction "GND_P6") (pintype "power_in"))
      (node (ref "U9") (pin "P7") (pinfunction "GND_P7") (pintype "power_in"))
    )
    (net (code "37") (name "ICM_FSYNC") (class "Default")
      (node (ref "Q5") (pin "3") (pinfunction "D_3") (pintype "bidirectional"))
    )
    (net (code "38") (name "ICM_FSYNC_1V8") (class "Default")
      (node (ref "Q5") (pin "2") (pinfunction "S_2") (pintype "bidirectional"))
      (node (ref "R18") (pin "1") (pinfunction "1_1") (pintype "passive"))
      (node (ref "U6") (pin "11") (pinfunction "FSYNC_11") (pintype "bidirectional"))
    )
    (net (code "39") (name "IO26") (class "Default")
      (node (ref "U11") (pin "NSS") (pinfunction "~{CS}_NSS") (pintype "bidirectional"))
    )
    (net (code "40") (name "IO27") (class "Default")
      (node (ref "U11") (pin "DIO2") (pinfunction "DIO2_DIO2") (pintype "bidirectional"))
    )
    (net (code "41") (name "IO32") (class "Default")
      (node (ref "U11") (pin "DIO1") (pinfunction "DIO1_DIO1") (pintype "bidirectional"))
    )
    (net (code "42") (name "IO33") (class "Default")
      (node (ref "U11") (pin "DIO0") (pinfunction "DIO0_DIO0") (pintype "bidirectional"))
    )
    (net (code "43") (name "NAU_A+") (class "Default")
      (node (ref "J5") (pin "4") (pinfunction "4_4") (pintype "passive"))
      (node (ref "J5") (pin "8") (pinfunction "4_8") (pintype "passive"))
      (node (ref "J7") (pin "4") (pinfunction "4_4") (pintype "passive"))
      (node (ref "R23") (pin "1") (pinfunction "1_1") (pintype "passive"))
    )
    (net (code "44") (name "NAU_A-") (class "Default")
      (node (ref "J5") (pin "3") (pinfunction "3_3") (pintype "passive"))
      (node (ref "J5") (pin "7") (pinfunction "3_7") (pintype "passive"))
      (node (ref "J7") (pin "5") (pinfunction "5_5") (pintype "passive"))
      (node (ref "R22") (pin "1") (pinfunction "1_1") (pintype "passive"))
    )
    (net (code "45") (name "NAU_B+") (class "Default")
      (node (ref "C21") (pin "2") (pinfunction "2_2") (pintype "passive"))
      (node (ref "J7") (pin "1") (pinfunction "1_1") (pintype "passive"))
      (node (ref "U12") (pin "5") (pinfunction "VIN2P_5") (pintype "bidirectional"))
    )
    (net (code "46") (name "NAU_B-") (class "Default")
      (node (ref "J7") (pin "2") (pinfunction "2_2") (pintype "passive"))
      (node (ref "NAU_CAP") (pin "2") (pinfunction "2_2") (pintype "passive"))
      (node (ref "U12") (pin "4") (pinfunction "VIN2N_4") (pintype "bidirectional"))
    )
    (net (code "47") (name "Net-(C21-Pad1)") (class "Default")
      (node (ref "C21") (pin "1") (pinfunction "1_1") (pintype "passive"))
      (node (ref "NAU_CAP") (pin "1") (pinfunction "1_1") (pintype "passive"))
    )
    (net (code "48") (name "Net-(CHG-Pad1)") (class "Default")
      (node (ref "CHG") (pin "1") (pinfunction "1_1") (pintype "passive"))
      (node (ref "R7") (pin "1") (pinfunction "1_1") (pintype "passive"))
    )
    (net (code "49") (name "Net-(CHG-Pad2)") (class "Default")
      (node (ref "CHG") (pin "2") (pinfunction "2_2") (pintype "passive"))
      (node (ref "D3") (pin "A") (pinfunction "A_A") (pintype "passive"))
    )
    (net (code "50") (name "Net-(CHG_I-Pad1)") (class "Default")
      (node (ref "CHG_I") (pin "1") (pinfunction "1_1") (pintype "passive"))
      (node (ref "R8") (pin "2") (pinfunction "2_2") (pintype "passive"))
    )
    (net (code "51") (name "Net-(CHG_I-Pad3)") (class "Default")
      (node (ref "CHG_I") (pin "3") (pinfunction "3_3") (pintype "passive"))
      (node (ref "R9") (pin "2") (pinfunction "2_2") (pintype "passive"))
    )
    (net (code "52") (name "Net-(D2-PadC)") (class "Default")
      (node (ref "D2") (pin "C") (pinfunction "C_C") (pintype "passive"))
      (node (ref "R10") (pin "2") (pinfunction "2_2") (pintype "passive"))
    )
    (net (code "53") (name "Net-(I2C-Pad1)") (class "Default")
      (node (ref "I2C") (pin "1") (pinfunction "1_1") (pintype "passive"))
      (node (ref "R12") (pin "2") (pinfunction "2_2") (pintype "passive"))
    )
    (net (code "54") (name "Net-(I2C-Pad3)") (class "Default")
      (node (ref "I2C") (pin "3") (pinfunction "3_3") (pintype "passive"))
      (node (ref "R11") (pin "2") (pinfunction "2_2") (pintype "passive"))
    )
    (net (code "55") (name "Net-(J1-CC1)") (class "Default")
      (node (ref "J1") (pin "A5") (pinfunction "CC1_A5") (pintype "bidirectional"))
      (node (ref "R2") (pin "2") (pinfunction "2_2") (pintype "passive"))
    )
    (net (code "56") (name "Net-(J1-CC2)") (class "Default")
      (node (ref "J1") (pin "B5") (pinfunction "CC2_B5") (pintype "bidirectional"))
      (node (ref "R1") (pin "2") (pinfunction "2_2") (pintype "passive"))
    )
    (net (code "57") (name "Net-(J1-SHLD-PadSHLD1)") (class "Default")
      (node (ref "J1") (pin "SHLD1") (pinfunction "SHLD_SHLD1") (pintype "bidirectional"))
      (node (ref "J1") (pin "SHLD2") (pinfunction "SHLD_SHLD2") (pintype "bidirectional"))
      (node (ref "J1") (pin "SHLD3") (pinfunction "SHLD_SHLD3") (pintype "bidirectional"))
      (node (ref "J1") (pin "SHLD4") (pinfunction "SHLD_SHLD4") (pintype "bidirectional"))
      (node (ref "SHLD") (pin "2") (pinfunction "2_2") (pintype "passive"))
    )
    (net (code "58") (name "Net-(J4-SIGNAL)") (class "Default")
      (node (ref "J4") (pin "FEED") (pinfunction "SIGNAL_FEED") (pintype "bidirectional"))
      (node (ref "U11") (pin "ANT") (pinfunction "ANT_ANT") (pintype "bidirectional"))
    )
    (net (code "59") (name "Net-(L1-1)") (class "Default")
      (node (ref "L1") (pin "P$1") (pinfunction "1_P$1") (pintype "passive"))
      (node (ref "U2") (pin "3") (pinfunction "LX_3") (pintype "input"))
    )
    (net (code "60") (name "Net-(PWR-Pad2)") (class "Default")
      (node (ref "PWR") (pin "2") (pinfunction "2_2") (pintype "passive"))
      (node (ref "R10") (pin "1") (pinfunction "1_1") (pintype "passive"))
    )
    (net (code "61") (name "Net-(Q1-S)") (class "Default")
      (node (ref "D1") (pin "C") (pinfunction "C_C") (pintype "passive"))
      (node (ref "MEAS") (pin "1") (pinfunction "1_1") (pintype "passive"))
      (node (ref "MEAS") (pin "3") (pinfunction "1_3") (pintype "passive"))
      (node (ref "Q1") (pin "2") (pinfunction "S_2") (pintype "bidirectional"))
    )
    (net (code "62") (name "Net-(Q6A-B)") (class "Default")
      (node (ref "Q6") (pin "5") (pinfunction "B_5") (pintype "passive"))
      (node (ref "R20") (pin "2") (pinfunction "2_2") (pintype "passive"))
    )
    (net (code "63") (name "Net-(Q6B-B)") (class "Default")
      (node (ref "Q6") (pin "2") (pinfunction "B_2") (pintype "passive"))
      (node (ref "R19") (pin "2") (pinfunction "2_2") (pintype "passive"))
    )
    (net (code "64") (name "Net-(U2-FB)") (class "Default")
      (node (ref "C2") (pin "1") (pinfunction "1_1") (pintype "passive"))
      (node (ref "R5") (pin "1") (pinfunction "1_1") (pintype "passive"))
      (node (ref "R6") (pin "2") (pinfunction "2_2") (pintype "passive"))
      (node (ref "U2") (pin "5") (pinfunction "FB_5") (pintype "passive"))
    )
    (net (code "65") (name "Net-(U2-VIN)") (class "Default")
      (node (ref "C1") (pin "1") (pinfunction "1_1") (pintype "passive"))
      (node (ref "MEAS") (pin "2") (pinfunction "2_2") (pintype "passive"))
      (node (ref "MEAS") (pin "4") (pinfunction "2_4") (pintype "passive"))
      (node (ref "R4") (pin "1") (pinfunction "1_1") (pintype "passive"))
      (node (ref "U2") (pin "4") (pinfunction "VIN_4") (pintype "input"))
    )
    (net (code "66") (name "Net-(U3-STAT)") (class "Default")
      (node (ref "D3") (pin "C") (pinfunction "C_C") (pintype "passive"))
      (node (ref "U3") (pin "1") (pinfunction "STAT_1") (pintype "output"))
    )
    (net (code "67") (name "Net-(U5-SDO{slash}ADR)") (class "Default")
      (node (ref "BME_ADR") (pin "2") (pinfunction "2_2") (pintype "passive"))
      (node (ref "R13") (pin "1") (pinfunction "1_1") (pintype "passive"))
      (node (ref "U5") (pin "5") (pinfunction "SDO/ADR_5") (pintype "bidirectional"))
    )
    (net (code "68") (name "Net-(U6-AD0{slash}SDO)") (class "Default")
      (node (ref "ICM_ADR") (pin "2") (pinfunction "2_2") (pintype "passive"))
      (node (ref "R14") (pin "1") (pinfunction "1_1") (pintype "passive"))
      (node (ref "U6") (pin "9") (pinfunction "AD0/SDO_9") (pintype "bidirectional"))
    )
    (net (code "69") (name "Net-(U6-REGOUT)") (class "Default")
      (node (ref "C13") (pin "1") (pinfunction "1_1") (pintype "passive"))
      (node (ref "U6") (pin "10") (pinfunction "REGOUT_10") (pintype "bidirectional"))
    )
    (net (code "70") (name "Net-(U9-SDO{slash}SA0)") (class "Default")
      (node (ref "ISM_ADR") (pin "2") (pinfunction "2_2") (pintype "passive"))
      (node (ref "R21") (pin "1") (pinfunction "1_1") (pintype "passive"))
      (node (ref "U9") (pin "P1") (pinfunction "SDO/SA0_P1") (pintype "bidirectional"))
    )
    (net (code "71") (name "Net-(U10-CAP)") (class "Default")
      (node (ref "C18") (pin "1") (pinfunction "1_1") (pintype "passive"))
      (node (ref "U10") (pin "10") (pinfunction "CAP_10") (pintype "passive"))
    )
    (net (code "72") (name "Net-(U12-VBG)") (class "Default")
      (node (ref "C19") (pin "1") (pinfunction "1_1") (pintype "passive"))
      (node (ref "U12") (pin "6") (pinfunction "VBG_6") (pintype "bidirectional"))
    )
    (net (code "73") (name "Net-(U12-VIN1N)") (class "Default")
      (node (ref "C20") (pin "1") (pinfunction "1_1") (pintype "passive"))
      (node (ref "R22") (pin "2") (pinfunction "2_2") (pintype "passive"))
      (node (ref "U12") (pin "2") (pinfunction "VIN1N_2") (pintype "bidirectional"))
    )
    (net (code "74") (name "Net-(U12-VIN1P)") (class "Default")
      (node (ref "C20") (pin "2") (pinfunction "2_2") (pintype "passive"))
      (node (ref "R23") (pin "2") (pinfunction "2_2") (pintype "passive"))
      (node (ref "U12") (pin "3") (pinfunction "VIN1P_3") (pintype "bidirectional"))
    )
    (net (code "75") (name "PICO") (class "Default")
      (node (ref "U1") (pin "16") (pinfunction "PICO2/IOA13_16") (pintype "bidirectional"))
      (node (ref "U11") (pin "SDI") (pinfunction "SDI_SDI") (pintype "bidirectional"))
    )
    (net (code "76") (name "POCI") (class "Default")
      (node (ref "U1") (pin "14") (pinfunction "POCI2/IOA12_14") (pintype "bidirectional"))
      (node (ref "U11") (pin "SDO") (pinfunction "SDO_SDO") (pintype "bidirectional"))
    )
    (net (code "77") (name "RTS") (class "Default")
      (node (ref "Q6") (pin "4") (pinfunction "E_4") (pintype "passive"))
      (node (ref "R19") (pin "1") (pinfunction "1_1") (pintype "passive"))
      (node (ref "U8") (pin "14") (pinfunction "~{RTS}_14") (pintype "bidirectional"))
    )
    (net (code "78") (name "SCK") (class "Default")
      (node (ref "U1") (pin "13") (pinfunction "SCK2/IOA14_13") (pintype "bidirectional"))
      (node (ref "U11") (pin "SCK") (pinfunction "SCK_SCK") (pintype "bidirectional"))
    )
    (net (code "79") (name "SCL") (class "Default")
      (node (ref "J3") (pin "4") (pinfunction "4_4") (pintype "passive"))
      (node (ref "Q3") (pin "3") (pinfunction "D_3") (pintype "bidirectional"))
      (node (ref "R11") (pin "1") (pinfunction "1_1") (pintype "passive"))
      (node (ref "U1") (pin "36") (pinfunction "SCL/IO22_36") (pintype "bidirectional"))
      (node (ref "U10") (pin "1") (pinfunction "SCL/SCK_1") (pintype "bidirectional"))
      (node (ref "U12") (pin "13") (pinfunction "SCLK_13") (pintype "bidirectional"))
      (node (ref "U4") (pin "7") (pinfunction "SCL_7") (pintype "output"))
      (node (ref "U5") (pin "4") (pinfunction "SCK/SCL_4") (pintype "bidirectional"))
      (node (ref "U9") (pin "P13") (pinfunction "SCL_P13") (pintype "bidirectional"))
    )
    (net (code "80") (name "SCL_1V8") (class "Default")
      (node (ref "Q3") (pin "2") (pinfunction "S_2") (pintype "bidirectional"))
      (node (ref "R16") (pin "1") (pinfunction "1_1") (pintype "passive"))
      (node (ref "U6") (pin "23") (pinfunction "SCL/SCLK_23") (pintype "bidirectional"))
    )
    (net (code "81") (name "SDA") (class "Default")
      (node (ref "J3") (pin "3") (pinfunction "3_3") (pintype "passive"))
      (node (ref "Q2") (pin "3") (pinfunction "D_3") (pintype "bidirectional"))
      (node (ref "R12") (pin "1") (pinfunction "1_1") (pintype "passive"))
      (node (ref "U1") (pin "33") (pinfunction "SDA/IO21_33") (pintype "bidirectional"))
      (node (ref "U10") (pin "16") (pinfunction "SDA/SDI_16") (pintype "bidirectional"))
      (node (ref "U12") (pin "14") (pinfunction "SDIO_14") (pintype "bidirectional"))
      (node (ref "U4") (pin "8") (pinfunction "SDA_8") (pintype "input"))
      (node (ref "U5") (pin "3") (pinfunction "SDI/SDA_3") (pintype "bidirectional"))
      (node (ref "U9") (pin "P14") (pinfunction "SDA/SDI/SDO_P14") (pintype "bidirectional"))
    )
    (net (code "82") (name "SDA_1V8") (class "Default")
      (node (ref "Q2") (pin "2") (pinfunction "S_2") (pintype "bidirectional"))
      (node (ref "R15") (pin "1") (pinfunction "1_1") (pintype "passive"))
      (node (ref "U6") (pin "24") (pinfunction "SDA/SDI_24") (pintype "bidirectional"))
    )
    (net (code "83") (name "USB_DN") (class "Default")
      (node (ref "J1") (pin "A7") (pinfunction "D-_A7") (pintype "bidirectional"))
      (node (ref "J1") (pin "B7") (pinfunction "D-_B7") (pintype "bidirectional"))
      (node (ref "U8") (pin "6") (pinfunction "UD-_6") (pintype "bidirectional"))
    )
    (net (code "84") (name "USB_DP") (class "Default")
      (node (ref "J1") (pin "A6") (pinfunction "D+_A6") (pintype "bidirectional"))
      (node (ref "J1") (pin "B6") (pinfunction "D+_B6") (pintype "bidirectional"))
      (node (ref "U8") (pin "5") (pinfunction "UD+_5") (pintype "bidirectional"))
    )
    (net (code "85") (name "VDDA") (class "Default")
      (node (ref "C22") (pin "1") (pinfunction "1_1") (pintype "passive"))
      (node (ref "C23") (pin "1") (pinfunction "1_1") (pintype "passive"))
      (node (ref "J5") (pin "1") (pinfunction "1_1") (pintype "passive"))
      (node (ref "J5") (pin "5") (pinfunction "1_5") (pintype "passive"))
      (node (ref "J7") (pin "7") (pinfunction "7_7") (pintype "passive"))
      (node (ref "U12") (pin "1") (pinfunction "REFP_1") (pintype "bidirectional"))
      (node (ref "U12") (pin "16") (pinfunction "AVDD_16") (pintype "bidirectional"))
    )
    (net (code "86") (name "V_BATT") (class "Default")
      (node (ref "C5") (pin "1") (pinfunction "1_1") (pintype "passive"))
      (node (ref "C6") (pin "1") (pinfunction "1_1") (pintype "passive"))
      (node (ref "CHG_I") (pin "2") (pinfunction "2_2") (pintype "passive"))
      (node (ref "J2") (pin "2") (pinfunction "+_2") (pintype "bidirectional"))
      (node (ref "J6") (pin "1") (pinfunction "1_1") (pintype "passive"))
      (node (ref "Q1") (pin "3") (pinfunction "D_3") (pintype "bidirectional"))
      (node (ref "U3") (pin "3") (pinfunction "VBAT_3") (pintype "power_in"))
      (node (ref "U4") (pin "2") (pinfunction "CELL_2") (pintype "input"))
      (node (ref "U4") (pin "3") (pinfunction "VDD_3") (pintype "bidirectional"))
    )
    (net (code "87") (name "V_USB") (class "Default")
      (node (ref "C4") (pin "1") (pinfunction "1_1") (pintype "passive"))
      (node (ref "D1") (pin "A") (pinfunction "A_A") (pintype "passive"))
      (node (ref "J1") (pin "VBUS1") (pinfunction "VBUS_VBUS1") (pintype "bidirectional"))
      (node (ref "J1") (pin "VBUS2") (pinfunction "VBUS_VBUS2") (pintype "bidirectional"))
      (node (ref "Q1") (pin "1") (pinfunction "G_1") (pintype "bidirectional"))
      (node (ref "R3") (pin "2") (pinfunction "2_2") (pintype "passive"))
      (node (ref "R7") (pin "2") (pinfunction "2_2") (pintype "passive"))
      (node (ref "U3") (pin "4") (pinfunction "VIN_4") (pintype "power_in"))
    )
    (net (code "88") (name "unconnected-(J2-PAD1-PadNC1)") (class "Default")
      (node (ref "J2") (pin "NC1") (pinfunction "PAD1_NC1") (pintype "bidirectional"))
    )
    (net (code "89") (name "unconnected-(J2-PAD2-PadNC2)") (class "Default")
      (node (ref "J2") (pin "NC2") (pinfunction "PAD2_NC2") (pintype "bidirectional"))
    )
    (net (code "90") (name "unconnected-(U3-PROG-Pad5)") (class "Default")
      (node (ref "U3") (pin "5") (pinfunction "PROG_5") (pintype "input"))
    )
    (net (code "91") (name "unconnected-(U6-AUX_CL-Pad7)") (class "Default")
      (node (ref "U6") (pin "7") (pinfunction "AUX_CL_7") (pintype "bidirectional"))
    )
    (net (code "92") (name "unconnected-(U6-AUX_DA-Pad21)") (class "Default")
      (node (ref "U6") (pin "21") (pinfunction "AUX_DA_21") (pintype "bidirectional"))
    )
    (net (code "93") (name "unconnected-(U8-R232-Pad15)") (class "Default")
      (node (ref "U8") (pin "15") (pinfunction "R232_15") (pintype "bidirectional"))
    )
    (net (code "94") (name "unconnected-(U8-~{CTS}-Pad9)") (class "Default")
      (node (ref "U8") (pin "9") (pinfunction "~{CTS}_9") (pintype "bidirectional"))
    )
    (net (code "95") (name "unconnected-(U8-~{DCD}-Pad12)") (class "Default")
      (node (ref "U8") (pin "12") (pinfunction "~{DCD}_12") (pintype "bidirectional"))
    )
    (net (code "96") (name "unconnected-(U8-~{DSR}-Pad10)") (class "Default")
      (node (ref "U8") (pin "10") (pinfunction "~{DSR}_10") (pintype "bidirectional"))
    )
    (net (code "97") (name "unconnected-(U8-~{RI}-Pad11)") (class "Default")
      (node (ref "U8") (pin "11") (pinfunction "~{RI}_11") (pintype "bidirectional"))
    )
    (net (code "98") (name "unconnected-(U9-OCS_AUX-PadP10)") (class "Default")
      (node (ref "U9") (pin "P10") (pinfunction "OCS_AUX_P10") (pintype "bidirectional"))
    )
    (net (code "99") (name "unconnected-(U9-SCX-PadP3)") (class "Default")
      (node (ref "U9") (pin "P3") (pinfunction "SCX_P3") (pintype "bidirectional"))
    )
    (net (code "100") (name "unconnected-(U9-SDO_AUX-PadP11)") (class "Default")
      (node (ref "U9") (pin "P11") (pinfunction "SDO_AUX_P11") (pintype "bidirectional"))
    )
    (net (code "101") (name "unconnected-(U9-SDX-PadP2)") (class "Default")
      (node (ref "U9") (pin "P2") (pinfunction "SDX_P2") (pintype "bidirectional"))
    )
    (net (code "102") (name "unconnected-(U10-SDO-Pad5)") (class "Default")
      (node (ref "U10") (pin "5") (pinfunction "SDO_5") (pintype "output"))
    )
    (net (code "103") (name "unconnected-(U11-PadDIO3)") (class "Default")
      (node (ref "U11") (pin "DIO3") (pinfunction "DIO3_DIO3") (pintype "bidirectional"))
    )
    (net (code "104") (name "unconnected-(U11-PadDIO4)") (class "Default")
      (node (ref "U11") (pin "DIO4") (pinfunction "DIO4_DIO4") (pintype "bidirectional"))
    )
    (net (code "105") (name "unconnected-(U11-PadDIO5)") (class "Default")
      (node (ref "U11") (pin "DIO5") (pinfunction "DIO5_DIO5") (pintype "bidirectional"))
    )
    (net (code "106") (name "unconnected-(U12-XIN-Pad10)") (class "Default")
      (node (ref "U12") (pin "10") (pinfunction "XIN_10") (pintype "bidirectional"))
    )
    (net (code "107") (name "unconnected-(U12-XOUT-Pad11)") (class "Default")
      (node (ref "U12") (pin "11") (pinfunction "XOUT_11") (pintype "bidirectional"))
    )
  )
)
